# QWIIC.net
KiCad netlist of a schematic drawn in Altium Designer
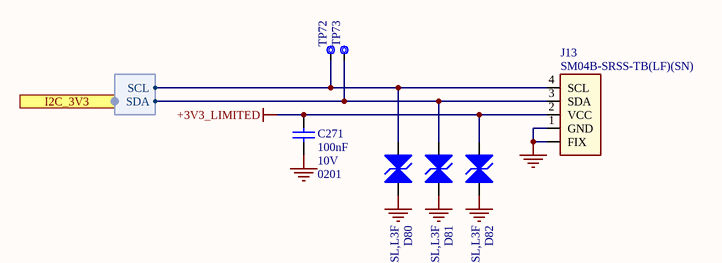
[diagram p0: QWIIC.SchDoc]

(export (version "E")
  (design (tool "Eeschema 10.0.6"))
  (components
    (comp (ref "C271")
      (value "100nF")
      (footprint "CAP-0201")
      (description "CAP CHIP 0201 100nF 10% 10V X5R")
      (fields
        (field (name "PART NUMBER") "CL03A104KP3NNNC")
        (field (name "MANUFACTURER") "Samsung Electro-Mechanics")
        (field (name "VOLTAGE") "10V")
        (field (name "CASE CODE (IMPERIAL)") "0201")
      )
      (libsource (lib "Clean") (part "CAP"))
    )
    (comp (ref "D80")
      (value "DF2B7ASL,L3F")
      (footprint "DF2B7ASL,L3F")
      (description "TVS BIDIRECTIONAL SMD Vr 5.5V, Vbr min 5.8V, 0.62x0.32mm")
      (fields (field (name "MANUFACTURER") "TOSHIBA"))
      (libsource (lib "Clean") (part "Diode TVS"))
    )
    (comp (ref "D81")
      (value "DF2B7ASL,L3F")
      (footprint "DF2B7ASL,L3F")
      (description "TVS BIDIRECTIONAL SMD Vr 5.5V, Vbr min 5.8V, 0.62x0.32mm")
      (fields (field (name "MANUFACTURER") "TOSHIBA"))
      (libsource (lib "Clean") (part "Diode TVS"))
    )
    (comp (ref "D82")
      (value "DF2B7ASL,L3F")
      (footprint "DF2B7ASL,L3F")
      (description "TVS BIDIRECTIONAL SMD Vr 5.5V, Vbr min 5.8V, 0.62x0.32mm")
      (fields (field (name "MANUFACTURER") "TOSHIBA"))
      (libsource (lib "Clean") (part "Diode TVS"))
    )
    (comp (ref "J13")
      (value "SM04B-SRSS-TB(LF)(SN)")
      (footprint "SM04B-SRSS-TB(LF)(SN)-Footprint-1")
      (description "CONN JST SH 1mm 4POS HORIZONTAL TIN QWIIC")
      (fields (field (name "MANUFACTURER") "JST") (field (name "LCSC PART #") "C160404"))
      (libsource (lib "Clean") (part "SM04B-SRSS-TB(LF)(SN)"))
    )
    (comp (ref "TP72")
      (value "Test point 1.00mm")
      (footprint "TP-1.00MM")
      (fields (field (name "PART NUMBER") "This is not a component"))
      (libsource (lib "Clean") (part "TESTPOINT"))
    )
    (comp (ref "TP73")
      (value "Test point 1.00mm")
      (footprint "TP-1.00MM")
      (fields (field (name "PART NUMBER") "This is not a component"))
      (libsource (lib "Clean") (part "TESTPOINT"))
    )
  )
  (nets
    (net (code "2") (name "+3V3_LIMITED") (class "Default")
      (node (ref "C271") (pin "2") (pinfunction "2_2") (pintype "passive"))
      (node (ref "D82") (pin "2") (pinfunction "A2_2") (pintype "passive"))
      (node (ref "J13") (pin "2") (pinfunction "VCC_2") (pintype "passive"))
    )
    (net (code "4") (name "GND") (class "Default")
      (node (ref "C271") (pin "1") (pinfunction "1_1") (pintype "passive"))
      (node (ref "D80") (pin "1") (pinfunction "A1_1") (pintype "passive"))
      (node (ref "D81") (pin "1") (pinfunction "A1_1") (pintype "passive"))
      (node (ref "D82") (pin "1") (pinfunction "A1_1") (pintype "passive"))
      (node (ref "J13") (pin "1") (pinfunction "GND_1") (pintype "passive"))
      (node (ref "J13") (pin "FIX") (pinfunction "FIX_FIX") (pintype "passive"))
    )
    (net (code "5") (name "Net-(D80-A2)") (class "Default")
      (node (ref "D80") (pin "2") (pinfunction "A2_2") (pintype "passive"))
      (node (ref "J13") (pin "4") (pinfunction "SCL_4") (pintype "passive"))
      (node (ref "TP72") (pin "X") (pinfunction "X_X") (pintype "passive"))
    )
    (net (code "6") (name "Net-(D81-A2)") (class "Default")
      (node (ref "D81") (pin "2") (pinfunction "A2_2") (pintype "passive"))
      (node (ref "J13") (pin "3") (pinfunction "SDA_3") (pintype "passive"))
      (node (ref "TP73") (pin "X") (pinfunction "X_X") (pintype "passive"))
    )
  )
)
